# BJT_switch.net
KiCad netlist of a schematic drawn in EAGLE
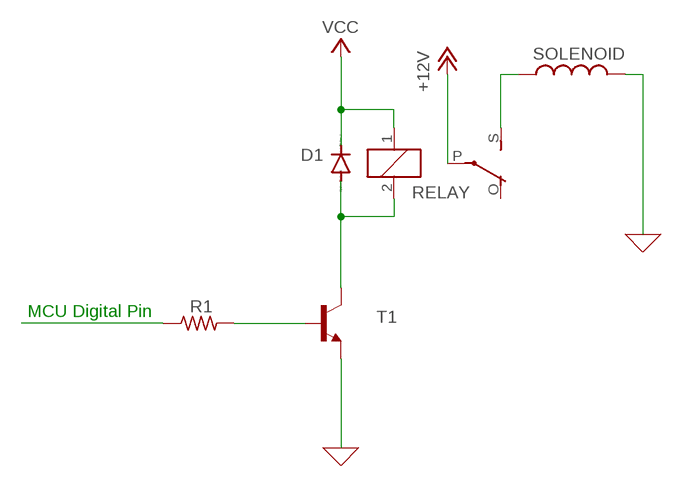
[diagram p0: schematic, sheet 1]

(export (version "E")
  (design (tool "Eeschema 10.0.6"))
  (components
    (comp (ref "D1")
      (value "1N4004")
      (footprint "eagle-import:DO41-10")
      (libsource (lib "eagle-import") (part "1N4004"))
    )
    (comp (ref "L1")
      (value "SOLENOID")
      (footprint "eagle-import:0207_5V")
      (libsource (lib "eagle-import") (part "L-US0207/5V"))
    )
    (comp (ref "R1")
      (value "R-US_0204/7")
      (footprint "eagle-import:0204_7")
      (libsource (lib "eagle-import") (part "R-US_0204/7"))
    )
    (comp (ref "RELAY")
      (value "ZF112")
      (footprint "eagle-import:ZF112")
      (libsource (lib "eagle-import") (part "ZF112"))
    )
    (comp (ref "T1")
      (value "-NPN-TO92")
      (footprint "eagle-import:TO92")
      (libsource (lib "eagle-import") (part "-NPN-TO92"))
    )
  )
  (nets
    (net (code "1") (name "+12V") (class "Default")
      (node (ref "RELAY") (pin "P") (pinfunction "P_P") (pintype "passive"))
    )
    (net (code "2") (name "GND") (class "Default")
      (node (ref "L1") (pin "2") (pinfunction "2_2") (pintype "passive"))
      (node (ref "T1") (pin "1") (pinfunction "E_1") (pintype "passive"))
    )
    (net (code "3") (name "Net-(L1-Pad1)") (class "Default")
      (node (ref "L1") (pin "1") (pinfunction "1_1") (pintype "passive"))
      (node (ref "RELAY") (pin "S") (pinfunction "S_S") (pintype "passive"))
    )
    (net (code "4") (name "Net-(T1-B)") (class "Default")
      (node (ref "R1") (pin "2") (pinfunction "2_2") (pintype "passive"))
      (node (ref "T1") (pin "2") (pinfunction "B_2") (pintype "passive"))
    )
    (net (code "5") (name "Net-(T1-C)") (class "Default")
      (node (ref "D1") (pin "A") (pinfunction "A_A") (pintype "passive"))
      (node (ref "RELAY") (pin "2") (pinfunction "2_2") (pintype "passive"))
      (node (ref "T1") (pin "3") (pinfunction "C_3") (pintype "passive"))
    )
    (net (code "6") (name "VCC") (class "Default")
      (node (ref "D1") (pin "C") (pinfunction "C_C") (pintype "passive"))
      (node (ref "RELAY") (pin "1") (pinfunction "1_1") (pintype "passive"))
    )
    (net (code "7") (name "unconnected-(R1-Pad1)") (class "Default")
      (node (ref "R1") (pin "1") (pinfunction "1_1") (pintype "passive"))
    )
    (net (code "8") (name "unconnected-(RELAY-PadO)") (class "Default")
      (node (ref "RELAY") (pin "O") (pinfunction "O_O") (pintype "passive"))
    )
  )
)
